# BUZZER.net
KiCad netlist of a schematic drawn in EAGLE
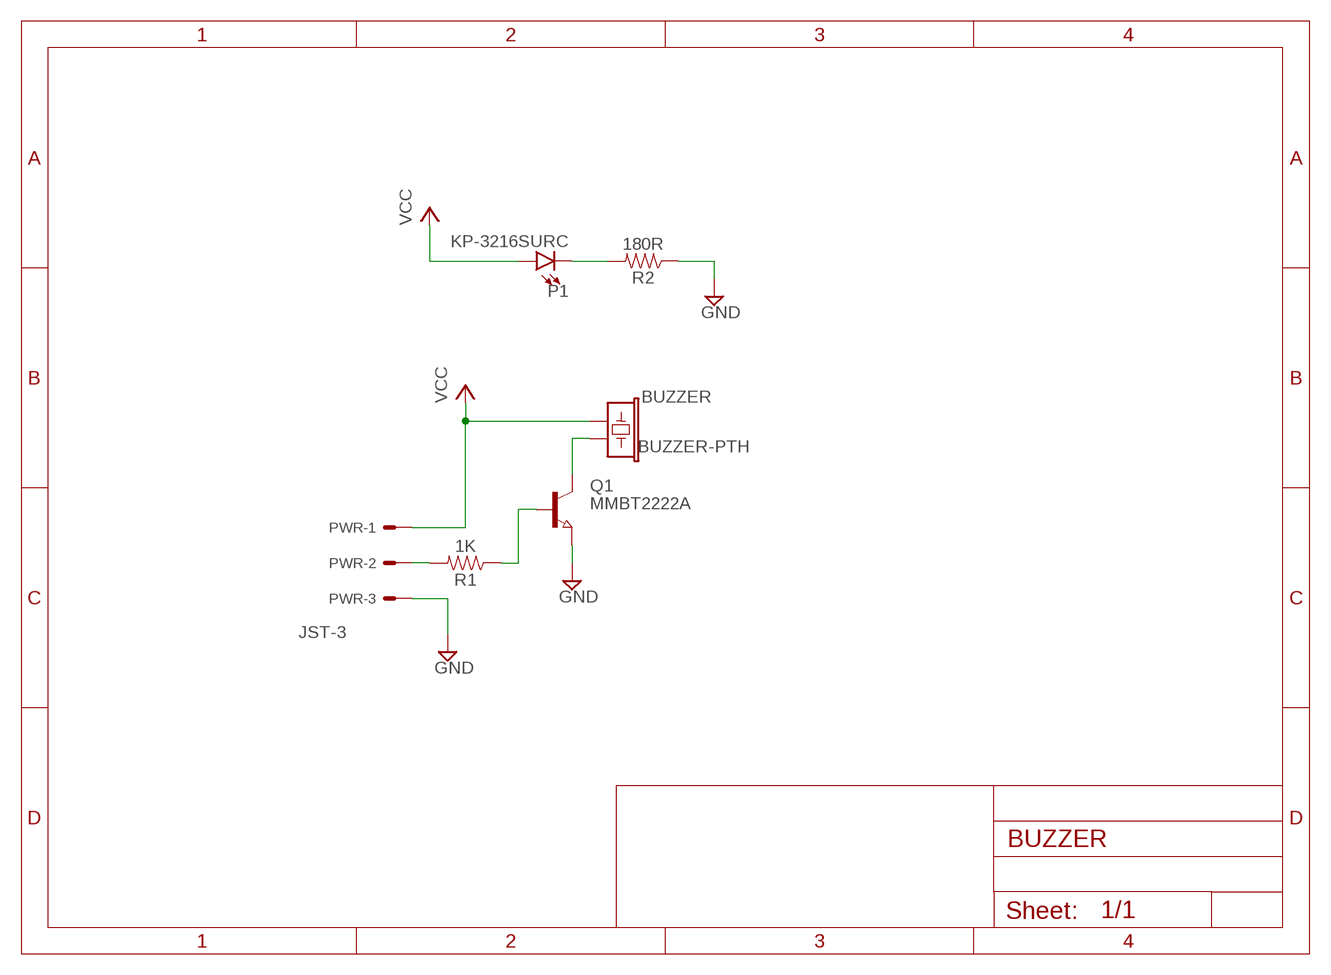
[diagram p0: schematic, sheet 1]

(export (version "E")
  (design (tool "Eeschema 10.0.6"))
  (components
    (comp (ref "BUZZER")
      (value "BUZZER-PTH")
      (footprint "eagle-import:BUZZER-12MM")
      (libsource (lib "eagle-import") (part "BUZZER-PTH"))
    )
    (comp (ref "P1")
      (value "KP-3216SURC")
      (footprint "eagle-import:LED_1206_BOSON")
      (fields (field (name "MANUFACTURER") "Kingbright") (field (name "PART_NO") "KP-3216SURC "))
      (libsource (lib "eagle-import") (part "LED_1206"))
    )
    (comp (ref "PWR")
      (value "JST-3")
      (footprint "eagle-import:JST-XH-03-PACKAGE-LONG-PAD")
      (libsource (lib "eagle-import") (part "JST-XH-03-PIN-LONG-PAD"))
    )
    (comp (ref "Q1")
      (value "MMBT2222A")
      (footprint "eagle-import:SOT_23_MMBT")
      (fields (field (name "MANUFACTURER") "DIODES INC"))
      (libsource (lib "eagle-import") (part "SOT-23_MMBT"))
    )
    (comp (ref "R1")
      (value "1K")
      (footprint "eagle-import:1206")
      (fields (field (name "MANUFACTURER") "RoyalOhm") (field (name "PART_NO") "1206S4J0102T5E "))
      (libsource (lib "eagle-import") (part "RESISTOR1206"))
    )
    (comp (ref "R2")
      (value "180R")
      (footprint "eagle-import:1206")
      (fields (field (name "MANUFACTURER") "TE Connectivity") (field (name "PART_NO") "CRG1206F180R "))
      (libsource (lib "eagle-import") (part "RESISTOR1206"))
    )
  )
  (nets
    (net (code "1") (name "GND") (class "Default")
      (node (ref "PWR") (pin "3") (pinfunction "S_3") (pintype "passive"))
      (node (ref "Q1") (pin "E") (pinfunction "E_E") (pintype "passive"))
      (node (ref "R2") (pin "1") (pinfunction "1_1") (pintype "passive"))
    )
    (net (code "2") (name "Net-(BUZZER-2)") (class "Default")
      (node (ref "BUZZER") (pin "-") (pinfunction "2_-") (pintype "passive"))
      (node (ref "Q1") (pin "C") (pinfunction "C_C") (pintype "passive"))
    )
    (net (code "3") (name "Net-(P1-C)") (class "Default")
      (node (ref "P1") (pin "P$2") (pinfunction "C_P$2") (pintype "passive"))
      (node (ref "R2") (pin "2") (pinfunction "2_2") (pintype "passive"))
    )
    (net (code "4") (name "Net-(PWRB-S)") (class "Default")
      (node (ref "PWR") (pin "2") (pinfunction "S_2") (pintype "passive"))
      (node (ref "R1") (pin "2") (pinfunction "2_2") (pintype "passive"))
    )
    (net (code "5") (name "Net-(Q1-PadB)") (class "Default")
      (node (ref "Q1") (pin "B") (pinfunction "B_B") (pintype "passive"))
      (node (ref "R1") (pin "1") (pinfunction "1_1") (pintype "passive"))
    )
    (net (code "6") (name "VCC") (class "Default")
      (node (ref "BUZZER") (pin "+") (pinfunction "1_+") (pintype "passive"))
      (node (ref "P1") (pin "P$1") (pinfunction "A_P$1") (pintype "passive"))
      (node (ref "PWR") (pin "1") (pinfunction "S_1") (pintype "passive"))
    )
  )
)
